# Sheet1.net
KiCad netlist of a schematic drawn in Altium Designer
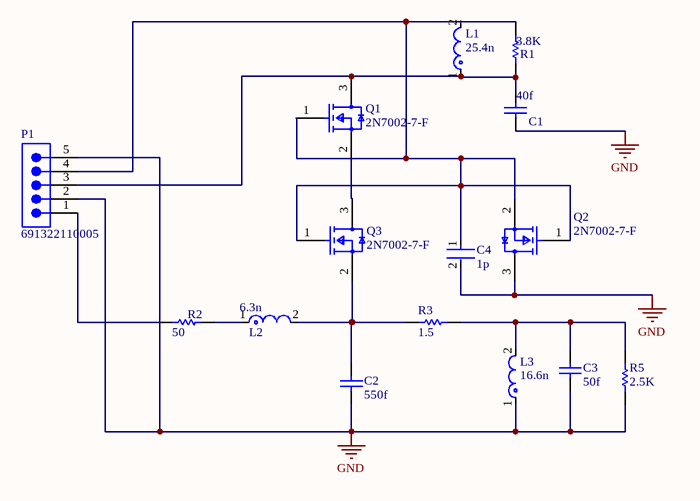
[diagram p0: Sheet1.SchDoc]

(export (version "E")
  (design (tool "Eeschema 10.0.6"))
  (components
    (comp (ref "C1")
      (value "40f")
      (footprint "CAPC1005X55X25ML05T10")
      (fields (field (name "PART NUMBER") "GRM1555C1H1R3CA01D") (field (name "MANUFACTURER") "Murata"))
      (libsource (lib "Altium Content Vault") (part "CAP"))
    )
    (comp (ref "C2")
      (value "550f")
      (footprint "CAPC1005X55X25ML05T10")
      (fields (field (name "PART NUMBER") "GRM1555C1H1R3CA01D") (field (name "MANUFACTURER") "Murata"))
      (libsource (lib "Altium Content Vault") (part "CAP"))
    )
    (comp (ref "C3")
      (value "50f")
      (footprint "CAPC1608X90X35NL10T15")
      (fields (field (name "PART NUMBER") "GQM1885C1H120JB01D") (field (name "MANUFACTURER") "Murata"))
      (libsource (lib "Altium Content Vault") (part "CAP"))
    )
    (comp (ref "C4")
      (value "1p")
      (footprint "FP-GJM155-0_05-IPC_B")
      (description "Multi-Layer Ceramic Capacitor 1pF C0G  ±0.1pF 0402 Paper T/R")
      (fields (field (name "VOLTAGE") "50V"))
      (libsource (lib "Altium Content Vault") (part "02cd4be3c70576c341d710602a673aa"))
    )
    (comp (ref "L1")
      (value "25.4n")
      (footprint "FP-LQP03TG_02-MFG")
      (description "Film type RF Inductor 3.3nH ±0.1nH 450mA 0.25Ω 0201 (0603)")
      (fields (field (name "TOLERANCE") "3%"))
      (libsource (lib "Altium Content Vault") (part "4cc4b267dca4c8e51f7102f422741d8"))
    )
    (comp (ref "L2")
      (value "6.3n")
      (footprint "FP-LQP03TG_02-MFG")
      (description "Film type RF Inductor 3.3nH ±0.1nH 450mA 0.25Ω 0201 (0603)")
      (fields (field (name "TOLERANCE") "3%"))
      (libsource (lib "Altium Content Vault") (part "4cc4b267dca4c8e51f7102f422741d8"))
    )
    (comp (ref "L3")
      (value "16.6n")
      (footprint "FP-LQP03TG_02-MFG")
      (description "Film type RF Inductor 3.3nH ±0.1nH 450mA 0.25Ω 0201 (0603)")
      (fields (field (name "TOLERANCE") "3%"))
      (libsource (lib "Altium Content Vault") (part "4cc4b267dca4c8e51f7102f422741d8"))
    )
    (comp (ref "P1")
      (value "691322110005")
      (footprint "691322110005")
      (fields (field (name "VOLTAGE") "300V"))
      (libsource (lib "Altium Content Vault") (part "TBL - 1R - 05P - Male"))
    )
    (comp (ref "Q1")
      (value "2N7002-7-F")
      (footprint "FP-SOT23-MFG")
      (description "MOSFET N-CH 60V 115MA SOT23-3")
      (fields (field (name "VOLTAGE") "60V"))
      (libsource (lib "Altium Content Vault") (part "3b9c635fedb024a5347a57b145af9cc"))
    )
    (comp (ref "Q2")
      (value "2N7002-7-F")
      (footprint "FP-SOT23-MFG")
      (description "MOSFET N-CH 60V 115MA SOT23-3")
      (fields (field (name "VOLTAGE") "60V"))
      (libsource (lib "Altium Content Vault") (part "3b9c635fedb024a5347a57b145af9cc"))
    )
    (comp (ref "Q3")
      (value "2N7002-7-F")
      (footprint "FP-SOT23-MFG")
      (description "MOSFET N-CH 60V 115MA SOT23-3")
      (fields (field (name "VOLTAGE") "60V"))
      (libsource (lib "Altium Content Vault") (part "3b9c635fedb024a5347a57b145af9cc"))
    )
    (comp (ref "R1")
      (value "3.8K")
      (footprint "RESC1005X40X25LL05T05")
      (description "Chip Resistor, 0 Ohm, 0.1 W, -55 to 155 degC, 0402 (1005 Metric), RoHS, Tape and Reel")
      (fields (field (name "MANUFACTURER") "Panasonic") (field (name "TOLERANCE") "5%"))
      (libsource (lib "Altium Content Vault") (part "RES-2"))
    )
    (comp (ref "R2")
      (value "50")
      (footprint "RESC1005X40X25LL05T05")
      (description "Chip Resistor, 0 Ohm, 0.1 W, -55 to 155 degC, 0402 (1005 Metric), RoHS, Tape and Reel")
      (fields (field (name "MANUFACTURER") "Panasonic") (field (name "TOLERANCE") "5%"))
      (libsource (lib "Altium Content Vault") (part "RES-2"))
    )
    (comp (ref "R3")
      (value "1.5")
      (footprint "RESC1005X40X25LL05T05")
      (description "Chip Resistor, 0 Ohm, 0.1 W, -55 to 155 degC, 0402 (1005 Metric), RoHS, Tape and Reel")
      (fields (field (name "MANUFACTURER") "Panasonic") (field (name "TOLERANCE") "5%"))
      (libsource (lib "Altium Content Vault") (part "RES-2"))
    )
    (comp (ref "R5")
      (value "2.5K")
      (footprint "RESC1005X40X25LL05T05")
      (description "Chip Resistor, 0 Ohm, 0.1 W, -55 to 155 degC, 0402 (1005 Metric), RoHS, Tape and Reel")
      (fields (field (name "MANUFACTURER") "Panasonic") (field (name "TOLERANCE") "5%"))
      (libsource (lib "Altium Content Vault") (part "RES-2"))
    )
  )
  (nets
    (net (code "1") (name "GND") (class "Default")
      (node (ref "C1") (pin "1") (pinfunction "1_1") (pintype "passive"))
      (node (ref "C2") (pin "1") (pinfunction "1_1") (pintype "passive"))
      (node (ref "C3") (pin "1") (pinfunction "1_1") (pintype "passive"))
      (node (ref "C4") (pin "2") (pinfunction "2_2") (pintype "passive"))
      (node (ref "L3") (pin "1") (pinfunction "1_1") (pintype "passive"))
      (node (ref "P1") (pin "2") (pinfunction "2_2") (pintype "passive"))
      (node (ref "P1") (pin "5") (pinfunction "5_5") (pintype "passive"))
      (node (ref "Q2") (pin "3") (pinfunction "D_3") (pintype "passive"))
      (node (ref "R5") (pin "1") (pinfunction "1_1") (pintype "passive"))
    )
    (net (code "2") (name "Net-(C3-Pad2)") (class "Default")
      (node (ref "C3") (pin "2") (pinfunction "2_2") (pintype "passive"))
      (node (ref "L3") (pin "2") (pinfunction "2_2") (pintype "passive"))
      (node (ref "R3") (pin "2") (pinfunction "2_2") (pintype "passive"))
      (node (ref "R5") (pin "2") (pinfunction "2_2") (pintype "passive"))
    )
    (net (code "3") (name "Net-(L2-Pad1)") (class "Default")
      (node (ref "L2") (pin "1") (pinfunction "1_1") (pintype "passive"))
      (node (ref "R2") (pin "2") (pinfunction "2_2") (pintype "passive"))
    )
    (net (code "4") (name "Net-(P1-Pad1)") (class "Default")
      (node (ref "P1") (pin "1") (pinfunction "1_1") (pintype "passive"))
      (node (ref "R2") (pin "1") (pinfunction "1_1") (pintype "passive"))
    )
    (net (code "5") (name "Net-(Q1-D)") (class "Default")
      (node (ref "C1") (pin "2") (pinfunction "2_2") (pintype "passive"))
      (node (ref "L1") (pin "1") (pinfunction "1_1") (pintype "passive"))
      (node (ref "P1") (pin "3") (pinfunction "3_3") (pintype "passive"))
      (node (ref "Q1") (pin "3") (pinfunction "D_3") (pintype "passive"))
      (node (ref "R1") (pin "1") (pinfunction "1_1") (pintype "passive"))
    )
    (net (code "6") (name "Net-(Q1-G)") (class "Default")
      (node (ref "C4") (pin "1") (pinfunction "1_1") (pintype "passive"))
      (node (ref "P1") (pin "4") (pinfunction "4_4") (pintype "passive"))
      (node (ref "Q1") (pin "1") (pinfunction "G_1") (pintype "passive"))
      (node (ref "Q2") (pin "1") (pinfunction "G_1") (pintype "passive"))
      (node (ref "Q2") (pin "2") (pinfunction "S_2") (pintype "passive"))
      (node (ref "Q3") (pin "1") (pinfunction "G_1") (pintype "passive"))
      (node (ref "R1") (pin "2") (pinfunction "2_2") (pintype "passive"))
    )
    (net (code "7") (name "Net-(Q1-S)") (class "Default")
      (node (ref "Q1") (pin "2") (pinfunction "S_2") (pintype "passive"))
      (node (ref "Q3") (pin "3") (pinfunction "D_3") (pintype "passive"))
    )
    (net (code "8") (name "Net-(Q3-S)") (class "Default")
      (node (ref "C2") (pin "2") (pinfunction "2_2") (pintype "passive"))
      (node (ref "L2") (pin "2") (pinfunction "2_2") (pintype "passive"))
      (node (ref "Q3") (pin "2") (pinfunction "S_2") (pintype "passive"))
      (node (ref "R3") (pin "1") (pinfunction "1_1") (pintype "passive"))
    )
    (net (code "9") (name "unconnected-(L1-Pad2)") (class "Default")
      (node (ref "L1") (pin "2") (pinfunction "2_2") (pintype "passive"))
    )
  )
)
